# ref.net
KiCad netlist of a schematic drawn in Altium Designer
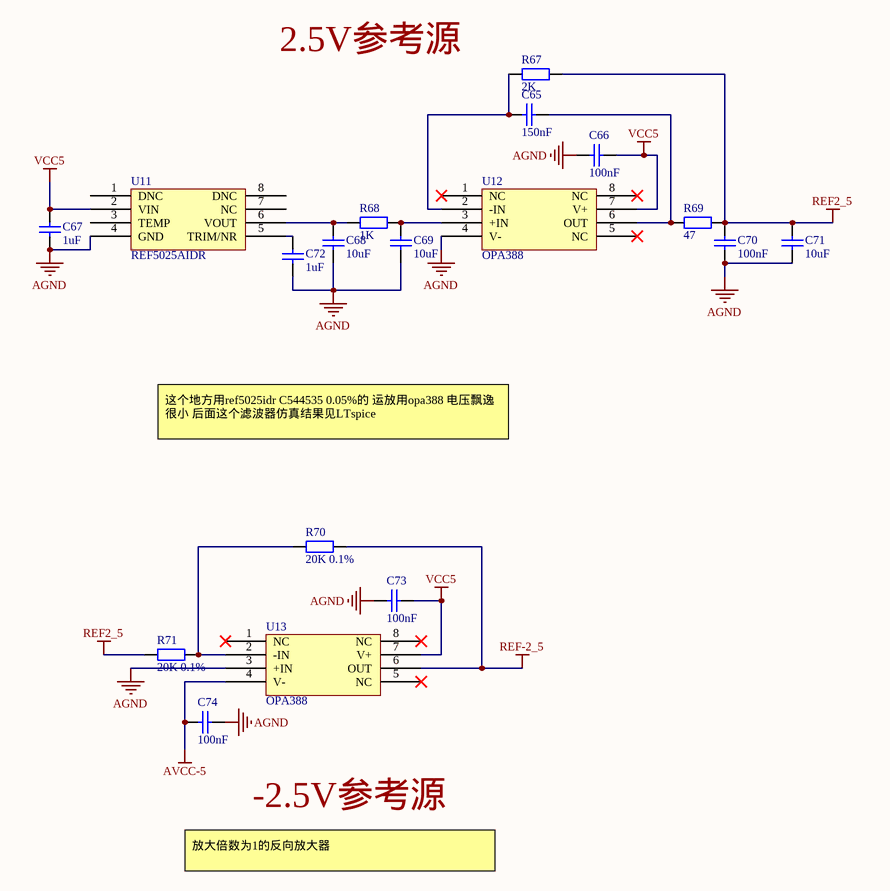
[diagram p0: ref.SchDoc]

(export (version "E")
  (design (tool "Eeschema 10.0.6"))
  (components
    (comp (ref "C65")
      (value "150nF")
      (footprint "C0603_L")
      (description "贴片电容/MLCC电容")
      (libsource (lib "0.1 - 电阻-电容-电感-保险丝-晶振-晶体-磁珠-电位器-法拉电容-馈通电容") (part "C"))
    )
    (comp (ref "C66")
      (value "100nF")
      (footprint "C0603_L")
      (description "贴片电容/MLCC电容")
      (libsource (lib "0.1 - 电阻-电容-电感-保险丝-晶振-晶体-磁珠-电位器-法拉电容-馈通电容") (part "C"))
    )
    (comp (ref "C67")
      (value "1uF")
      (footprint "C0603_L")
      (description "贴片电容/MLCC电容")
      (libsource (lib "0.1 - 电阻-电容-电感-保险丝-晶振-晶体-磁珠-电位器-法拉电容-馈通电容") (part "C"))
    )
    (comp (ref "C68")
      (value "10uF")
      (footprint "C0603_L")
      (description "贴片电容/MLCC电容")
      (libsource (lib "0.1 - 电阻-电容-电感-保险丝-晶振-晶体-磁珠-电位器-法拉电容-馈通电容") (part "C"))
    )
    (comp (ref "C69")
      (value "10uF")
      (footprint "C0603_L")
      (description "贴片电容/MLCC电容")
      (libsource (lib "0.1 - 电阻-电容-电感-保险丝-晶振-晶体-磁珠-电位器-法拉电容-馈通电容") (part "C"))
    )
    (comp (ref "C70")
      (value "100nF")
      (footprint "C0603_L")
      (description "贴片电容/MLCC电容")
      (libsource (lib "0.1 - 电阻-电容-电感-保险丝-晶振-晶体-磁珠-电位器-法拉电容-馈通电容") (part "C"))
    )
    (comp (ref "C71")
      (value "10uF")
      (footprint "C0603_L")
      (description "贴片电容/MLCC电容")
      (libsource (lib "0.1 - 电阻-电容-电感-保险丝-晶振-晶体-磁珠-电位器-法拉电容-馈通电容") (part "C"))
    )
    (comp (ref "C72")
      (value "1uF")
      (footprint "C0603_L")
      (description "贴片电容/MLCC电容")
      (libsource (lib "0.1 - 电阻-电容-电感-保险丝-晶振-晶体-磁珠-电位器-法拉电容-馈通电容") (part "C"))
    )
    (comp (ref "C73")
      (value "100nF")
      (footprint "C0603_L")
      (description "贴片电容/MLCC电容")
      (libsource (lib "0.1 - 电阻-电容-电感-保险丝-晶振-晶体-磁珠-电位器-法拉电容-馈通电容") (part "C"))
    )
    (comp (ref "C74")
      (value "100nF")
      (footprint "C0603_L")
      (description "贴片电容/MLCC电容")
      (libsource (lib "0.1 - 电阻-电容-电感-保险丝-晶振-晶体-磁珠-电位器-法拉电容-馈通电容") (part "C"))
    )
    (comp (ref "R67")
      (value "2K")
      (footprint "R0603_L")
      (description "贴片电阻")
      (libsource (lib "0.1 - 电阻-电容-电感-保险丝-晶振-晶体-磁珠-电位器-法拉电容-馈通电容") (part "R"))
    )
    (comp (ref "R68")
      (value "1K")
      (footprint "R0603_L")
      (description "贴片电阻")
      (libsource (lib "0.1 - 电阻-电容-电感-保险丝-晶振-晶体-磁珠-电位器-法拉电容-馈通电容") (part "R"))
    )
    (comp (ref "R69")
      (value "47")
      (footprint "R0603_L")
      (description "贴片电阻")
      (libsource (lib "0.1 - 电阻-电容-电感-保险丝-晶振-晶体-磁珠-电位器-法拉电容-馈通电容") (part "R"))
    )
    (comp (ref "R70")
      (value "20K 0.1%")
      (footprint "R0603_L")
      (description "贴片电阻")
      (libsource (lib "0.1 - 电阻-电容-电感-保险丝-晶振-晶体-磁珠-电位器-法拉电容-馈通电容") (part "R"))
    )
    (comp (ref "R71")
      (value "20K 0.1%")
      (footprint "R0603_L")
      (description "贴片电阻")
      (libsource (lib "0.1 - 电阻-电容-电感-保险丝-晶振-晶体-磁珠-电位器-法拉电容-馈通电容") (part "R"))
    )
    (comp (ref "U11")
      (value "REF5025AIDR")
      (footprint "SOIC-8")
      (description "2.5V、3μVpp/V 噪声、3ppm/°C 温漂、精密串联电压基准")
      (libsource (lib "HT") (part "REF5025AIDR"))
    )
    (comp (ref "U12")
      (value "OPA388")
      (footprint "SOIC-8")
      (description "OPA388 单路、10MHz、CMOS、零温漂、零交叉、真 RRIO 精密运算放大器")
      (libsource (lib "HT") (part "OPA388"))
    )
    (comp (ref "U13")
      (value "OPA388")
      (footprint "SOIC-8")
      (description "OPA388 单路、10MHz、CMOS、零温漂、零交叉、真 RRIO 精密运算放大器")
      (libsource (lib "HT") (part "OPA388"))
    )
  )
  (nets
    (net (code "1") (name "AGND") (class "Default")
      (node (ref "C66") (pin "2") (pinfunction "2_2") (pintype "passive"))
      (node (ref "C67") (pin "1") (pinfunction "1_1") (pintype "passive"))
      (node (ref "C68") (pin "1") (pinfunction "1_1") (pintype "passive"))
      (node (ref "C69") (pin "1") (pinfunction "1_1") (pintype "passive"))
      (node (ref "C70") (pin "2") (pinfunction "2_2") (pintype "passive"))
      (node (ref "C71") (pin "2") (pinfunction "2_2") (pintype "passive"))
      (node (ref "C72") (pin "1") (pinfunction "1_1") (pintype "passive"))
      (node (ref "C73") (pin "1") (pinfunction "1_1") (pintype "passive"))
      (node (ref "C74") (pin "1") (pinfunction "1_1") (pintype "passive"))
      (node (ref "U11") (pin "4") (pinfunction "GND_4") (pintype "passive"))
      (node (ref "U12") (pin "4") (pinfunction "V-_4") (pintype "passive"))
      (node (ref "U13") (pin "3") (pinfunction "+IN_3") (pintype "passive"))
    )
    (net (code "2") (name "AVCC-5") (class "Default")
      (node (ref "C74") (pin "2") (pinfunction "2_2") (pintype "passive"))
      (node (ref "U13") (pin "4") (pinfunction "V-_4") (pintype "passive"))
    )
    (net (code "3") (name "Net-(U11-TRIM{slash}NR)") (class "Default")
      (node (ref "C72") (pin "2") (pinfunction "2_2") (pintype "passive"))
      (node (ref "U11") (pin "5") (pinfunction "TRIM/NR_5") (pintype "passive"))
    )
    (net (code "4") (name "Net-(U11-VOUT)") (class "Default")
      (node (ref "C68") (pin "2") (pinfunction "2_2") (pintype "passive"))
      (node (ref "R68") (pin "1") (pinfunction "1_1") (pintype "passive"))
      (node (ref "U11") (pin "6") (pinfunction "VOUT_6") (pintype "passive"))
    )
    (net (code "5") (name "Net-(U12-+IN)") (class "Default")
      (node (ref "C69") (pin "2") (pinfunction "2_2") (pintype "passive"))
      (node (ref "R68") (pin "2") (pinfunction "2_2") (pintype "passive"))
      (node (ref "U12") (pin "3") (pinfunction "+IN_3") (pintype "passive"))
    )
    (net (code "6") (name "Net-(U12--IN)") (class "Default")
      (node (ref "C65") (pin "1") (pinfunction "1_1") (pintype "passive"))
      (node (ref "R67") (pin "1") (pinfunction "1_1") (pintype "passive"))
      (node (ref "U12") (pin "2") (pinfunction "-IN_2") (pintype "passive"))
    )
    (net (code "7") (name "Net-(U12-OUT)") (class "Default")
      (node (ref "C65") (pin "2") (pinfunction "2_2") (pintype "passive"))
      (node (ref "R69") (pin "1") (pinfunction "1_1") (pintype "passive"))
      (node (ref "U12") (pin "6") (pinfunction "OUT_6") (pintype "passive"))
    )
    (net (code "8") (name "Net-(U13--IN)") (class "Default")
      (node (ref "R70") (pin "1") (pinfunction "1_1") (pintype "passive"))
      (node (ref "R71") (pin "2") (pinfunction "2_2") (pintype "passive"))
      (node (ref "U13") (pin "2") (pinfunction "-IN_2") (pintype "passive"))
    )
    (net (code "9") (name "REF-2_5") (class "Default")
      (node (ref "R70") (pin "2") (pinfunction "2_2") (pintype "passive"))
      (node (ref "U13") (pin "6") (pinfunction "OUT_6") (pintype "passive"))
    )
    (net (code "10") (name "REF2_5") (class "Default")
      (node (ref "C70") (pin "1") (pinfunction "1_1") (pintype "passive"))
      (node (ref "C71") (pin "1") (pinfunction "1_1") (pintype "passive"))
      (node (ref "R67") (pin "2") (pinfunction "2_2") (pintype "passive"))
      (node (ref "R69") (pin "2") (pinfunction "2_2") (pintype "passive"))
      (node (ref "R71") (pin "1") (pinfunction "1_1") (pintype "passive"))
    )
    (net (code "11") (name "VCC5") (class "Default")
      (node (ref "C66") (pin "1") (pinfunction "1_1") (pintype "passive"))
      (node (ref "C67") (pin "2") (pinfunction "2_2") (pintype "passive"))
      (node (ref "C73") (pin "2") (pinfunction "2_2") (pintype "passive"))
      (node (ref "U11") (pin "2") (pinfunction "VIN_2") (pintype "passive"))
      (node (ref "U12") (pin "7") (pinfunction "V+_7") (pintype "passive"))
      (node (ref "U13") (pin "7") (pinfunction "V+_7") (pintype "passive"))
    )
    (net (code "12") (name "unconnected-(U11-DNC-Pad1)") (class "Default")
      (node (ref "U11") (pin "1") (pinfunction "DNC_1") (pintype "passive"))
    )
    (net (code "13") (name "unconnected-(U11-DNC-Pad8)") (class "Default")
      (node (ref "U11") (pin "8") (pinfunction "DNC_8") (pintype "passive"))
    )
    (net (code "14") (name "unconnected-(U11-NC-Pad7)") (class "Default")
      (node (ref "U11") (pin "7") (pinfunction "NC_7") (pintype "passive"))
    )
    (net (code "15") (name "unconnected-(U11-TEMP-Pad3)") (class "Default")
      (node (ref "U11") (pin "3") (pinfunction "TEMP_3") (pintype "passive"))
    )
    (net (code "16") (name "unconnected-(U12-NC-Pad1)") (class "Default")
      (node (ref "U12") (pin "1") (pinfunction "NC_1") (pintype "passive+no_connect"))
    )
    (net (code "17") (name "unconnected-(U12-NC-Pad5)") (class "Default")
      (node (ref "U12") (pin "5") (pinfunction "NC_5") (pintype "passive+no_connect"))
    )
    (net (code "18") (name "unconnected-(U12-NC-Pad8)") (class "Default")
      (node (ref "U12") (pin "8") (pinfunction "NC_8") (pintype "passive+no_connect"))
    )
    (net (code "19") (name "unconnected-(U13-NC-Pad1)") (class "Default")
      (node (ref "U13") (pin "1") (pinfunction "NC_1") (pintype "passive+no_connect"))
    )
    (net (code "20") (name "unconnected-(U13-NC-Pad5)") (class "Default")
      (node (ref "U13") (pin "5") (pinfunction "NC_5") (pintype "passive+no_connect"))
    )
    (net (code "21") (name "unconnected-(U13-NC-Pad8)") (class "Default")
      (node (ref "U13") (pin "8") (pinfunction "NC_8") (pintype "passive+no_connect"))
    )
  )
)
